# working.net
KiCad netlist of a schematic drawn in EAGLE
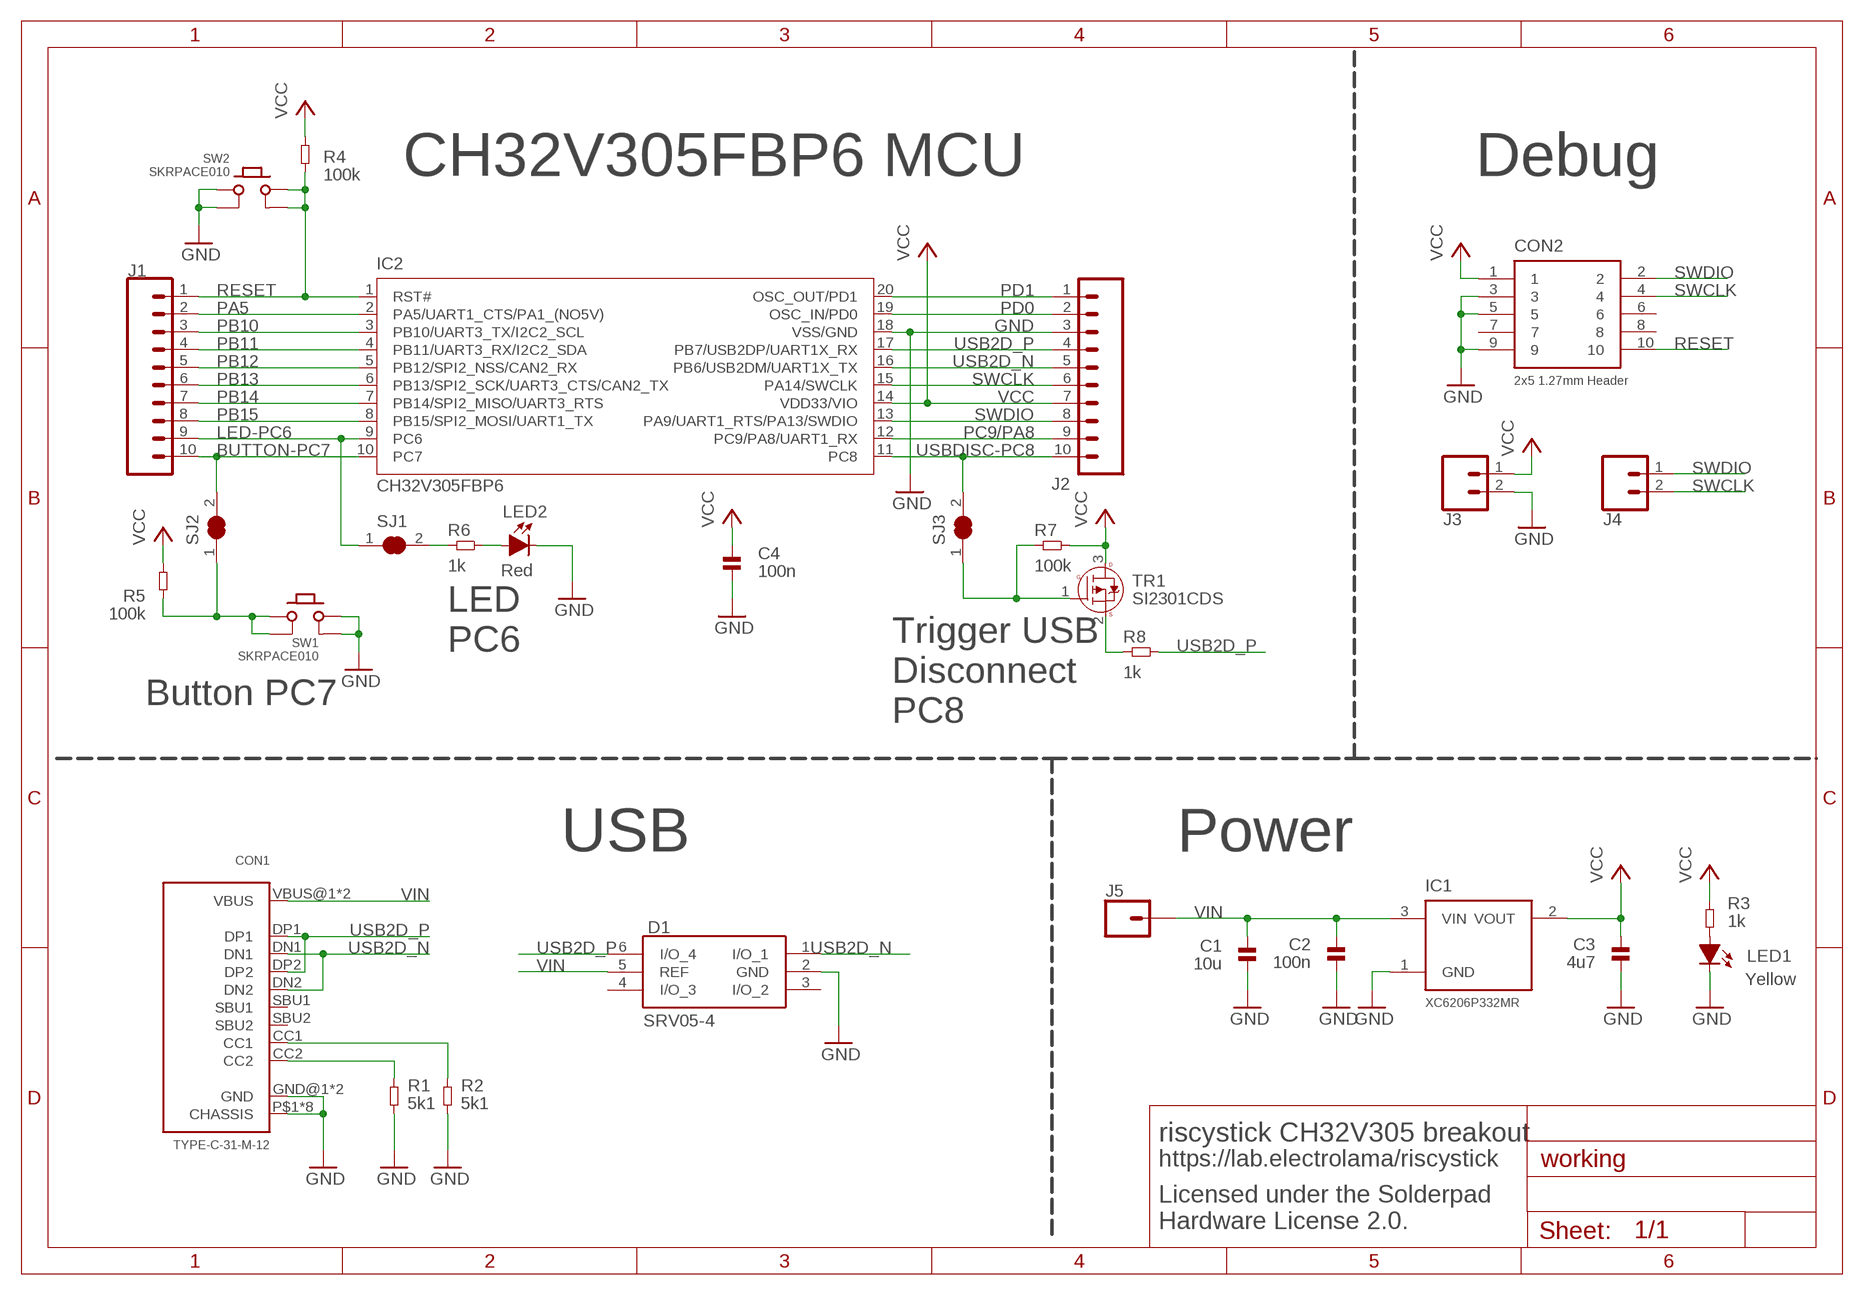
[diagram p0: schematic, sheet 1]

(export (version "E")
  (design (tool "Eeschema 10.0.6"))
  (components
    (comp (ref "C1")
      (value "10u")
      (footprint "eagle-import:_PKG_C_0603")
      (libsource (lib "eagle-import") (part "CAP-0603"))
    )
    (comp (ref "C2")
      (value "100n")
      (footprint "eagle-import:_PKG_C_0402")
      (libsource (lib "eagle-import") (part "CAP-0402"))
    )
    (comp (ref "C3")
      (value "4u7")
      (footprint "eagle-import:_PKG_C_0402")
      (libsource (lib "eagle-import") (part "CAP-0402"))
    )
    (comp (ref "C4")
      (value "100n")
      (footprint "eagle-import:_PKG_C_0402")
      (libsource (lib "eagle-import") (part "CAP-0402"))
    )
    (comp (ref "CON1")
      (value "TYPE-C-31-M-12")
      (footprint "eagle-import:USBC_C-31-M-12")
      (libsource (lib "eagle-import") (part "USBC_USB-C-12"))
    )
    (comp (ref "CON2")
      (value "2x5 1.27mm Header")
      (footprint "eagle-import:PZ127VS-12-10-H10-A38")
      (libsource (lib "eagle-import") (part "CON_1.27MM_SMD_2X5_NOSHROUD"))
    )
    (comp (ref "D1")
      (value "SRV05-4")
      (footprint "eagle-import:SOT95P280X145-6N")
      (fields (field (name "MANUFACTURER_PART_NUMBER") "SRV05-4-P-T7"))
      (libsource (lib "eagle-import") (part "DIODE-TVS-SRV05-4"))
    )
    (comp (ref "IC1")
      (value "XC6206P332MR")
      (footprint "eagle-import:SOT96P237X111-3N")
      (libsource (lib "eagle-import") (part "POWER-LDO-XC6206P???MR"))
    )
    (comp (ref "IC2")
      (value "CH32V305FBP6")
      (footprint "eagle-import:TSSOP20-WCH")
      (libsource (lib "eagle-import") (part "MCU-CH32V305F"))
    )
    (comp (ref "J1")
      (value "CONN_10LOCK")
      (footprint "eagle-import:1X10_LOCK")
      (libsource (lib "eagle-import") (part "CONN_10LOCK"))
    )
    (comp (ref "J2")
      (value "CONN_10LOCK")
      (footprint "eagle-import:1X10_LOCK")
      (libsource (lib "eagle-import") (part "CONN_10LOCK"))
    )
    (comp (ref "J3")
      (value "CONN_02LOCK")
      (footprint "eagle-import:1X02_LOCK")
      (libsource (lib "eagle-import") (part "CONN_02LOCK"))
    )
    (comp (ref "J4")
      (value "CONN_02LOCK")
      (footprint "eagle-import:1X02_LOCK")
      (libsource (lib "eagle-import") (part "CONN_02LOCK"))
    )
    (comp (ref "J5")
      (value "CONN_01")
      (footprint "eagle-import:1X01")
      (libsource (lib "eagle-import") (part "CONN_01"))
    )
    (comp (ref "LED1")
      (value "Yellow")
      (footprint "eagle-import:_PKG_LED_0805")
      (libsource (lib "eagle-import") (part "LED-0805"))
    )
    (comp (ref "LED2")
      (value "Red")
      (footprint "eagle-import:_PKG_LED_0805")
      (libsource (lib "eagle-import") (part "LED-0805"))
    )
    (comp (ref "R1")
      (value "5k1")
      (footprint "eagle-import:_PKG_R_0402")
      (libsource (lib "eagle-import") (part "RES-0402"))
    )
    (comp (ref "R2")
      (value "5k1")
      (footprint "eagle-import:_PKG_R_0402")
      (libsource (lib "eagle-import") (part "RES-0402"))
    )
    (comp (ref "R3")
      (value "1k")
      (footprint "eagle-import:_PKG_R_0402")
      (libsource (lib "eagle-import") (part "RES-0402"))
    )
    (comp (ref "R4")
      (value "100k")
      (footprint "eagle-import:_PKG_R_0402")
      (libsource (lib "eagle-import") (part "RES-0402"))
    )
    (comp (ref "R5")
      (value "100k")
      (footprint "eagle-import:_PKG_R_0402")
      (libsource (lib "eagle-import") (part "RES-0402"))
    )
    (comp (ref "R6")
      (value "1k")
      (footprint "eagle-import:_PKG_R_0402")
      (libsource (lib "eagle-import") (part "RES-0402"))
    )
    (comp (ref "R7")
      (value "100k")
      (footprint "eagle-import:_PKG_R_0402")
      (libsource (lib "eagle-import") (part "RES-0402"))
    )
    (comp (ref "R8")
      (value "1k")
      (footprint "eagle-import:_PKG_R_0402")
      (libsource (lib "eagle-import") (part "RES-0402"))
    )
    (comp (ref "SJ1")
      (value "SJ-SHORT")
      (footprint "eagle-import:SJ-SHORT")
      (libsource (lib "eagle-import") (part "SJ-SHORT"))
    )
    (comp (ref "SJ2")
      (value "SJ-SHORT")
      (footprint "eagle-import:SJ-SHORT")
      (libsource (lib "eagle-import") (part "SJ-SHORT"))
    )
    (comp (ref "SJ3")
      (value "SJ-SHORT")
      (footprint "eagle-import:SJ-SHORT")
      (libsource (lib "eagle-import") (part "SJ-SHORT"))
    )
    (comp (ref "SW1")
      (value "SKRPACE010")
      (footprint "eagle-import:PUSHBUTTON-4.2X3.2MM")
      (libsource (lib "eagle-import") (part "PUSHBUTTON-4.2X3.2MM"))
    )
    (comp (ref "SW2")
      (value "SKRPACE010")
      (footprint "eagle-import:PUSHBUTTON-4.2X3.2MM")
      (libsource (lib "eagle-import") (part "PUSHBUTTON-4.2X3.2MM"))
    )
    (comp (ref "TR1")
      (value "SI2301CDS")
      (footprint "eagle-import:SOT96P237X111-3N")
      (libsource (lib "eagle-import") (part "MOSFET-P-SI2301CDS"))
    )
  )
  (nets
    (net (code "1") (name "/BUTTON-PC7") (class "Default")
      (node (ref "IC2") (pin "10") (pinfunction "PC7_10") (pintype "bidirectional"))
      (node (ref "J1") (pin "10") (pinfunction "10_10") (pintype "passive"))
      (node (ref "SJ2") (pin "2") (pinfunction "2_2") (pintype "passive"))
    )
    (net (code "2") (name "/LED-PC6") (class "Default")
      (node (ref "IC2") (pin "9") (pinfunction "PC6_9") (pintype "bidirectional"))
      (node (ref "J1") (pin "9") (pinfunction "9_9") (pintype "passive"))
      (node (ref "SJ1") (pin "1") (pinfunction "1_1") (pintype "passive"))
    )
    (net (code "3") (name "/PA5") (class "Default")
      (node (ref "IC2") (pin "2") (pinfunction "PA5/UART1_CTS/PA1_(NO5V)_2") (pintype "bidirectional"))
      (node (ref "J1") (pin "2") (pinfunction "2_2") (pintype "passive"))
    )
    (net (code "4") (name "/PB10") (class "Default")
      (node (ref "IC2") (pin "3") (pinfunction "PB10/UART3_TX/I2C2_SCL_3") (pintype "bidirectional"))
      (node (ref "J1") (pin "3") (pinfunction "3_3") (pintype "passive"))
    )
    (net (code "5") (name "/PB11") (class "Default")
      (node (ref "IC2") (pin "4") (pinfunction "PB11/UART3_RX/I2C2_SDA_4") (pintype "bidirectional"))
      (node (ref "J1") (pin "4") (pinfunction "4_4") (pintype "passive"))
    )
    (net (code "6") (name "/PB12") (class "Default")
      (node (ref "IC2") (pin "5") (pinfunction "PB12/SPI2_NSS/CAN2_RX_5") (pintype "bidirectional"))
      (node (ref "J1") (pin "5") (pinfunction "5_5") (pintype "passive"))
    )
    (net (code "7") (name "/PB13") (class "Default")
      (node (ref "IC2") (pin "6") (pinfunction "PB13/SPI2_SCK/UART3_CTS/CAN2_TX_6") (pintype "bidirectional"))
      (node (ref "J1") (pin "6") (pinfunction "6_6") (pintype "passive"))
    )
    (net (code "8") (name "/PB14") (class "Default")
      (node (ref "IC2") (pin "7") (pinfunction "PB14/SPI2_MISO/UART3_RTS_7") (pintype "bidirectional"))
      (node (ref "J1") (pin "7") (pinfunction "7_7") (pintype "passive"))
    )
    (net (code "9") (name "/PB15") (class "Default")
      (node (ref "IC2") (pin "8") (pinfunction "PB15/SPI2_MOSI/UART1_TX_8") (pintype "bidirectional"))
      (node (ref "J1") (pin "8") (pinfunction "8_8") (pintype "passive"))
    )
    (net (code "10") (name "/PC9{slash}PA8") (class "Default")
      (node (ref "IC2") (pin "12") (pinfunction "PC9/PA8/UART1_RX_12") (pintype "bidirectional"))
      (node (ref "J2") (pin "9") (pinfunction "9_9") (pintype "passive"))
    )
    (net (code "11") (name "/PD0") (class "Default")
      (node (ref "IC2") (pin "19") (pinfunction "OSC_IN/PD0_19") (pintype "bidirectional"))
      (node (ref "J2") (pin "2") (pinfunction "2_2") (pintype "passive"))
    )
    (net (code "12") (name "/PD1") (class "Default")
      (node (ref "IC2") (pin "20") (pinfunction "OSC_OUT/PD1_20") (pintype "bidirectional"))
      (node (ref "J2") (pin "1") (pinfunction "1_1") (pintype "passive"))
    )
    (net (code "13") (name "/RESET") (class "Default")
      (node (ref "CON2") (pin "10") (pinfunction "10_10") (pintype "bidirectional"))
      (node (ref "IC2") (pin "1") (pinfunction "RST#_1") (pintype "bidirectional"))
      (node (ref "J1") (pin "1") (pinfunction "1_1") (pintype "passive"))
      (node (ref "R4") (pin "2") (pinfunction "2_2") (pintype "passive"))
      (node (ref "SW2") (pin "3") (pinfunction "2_1_3") (pintype "bidirectional"))
      (node (ref "SW2") (pin "4") (pinfunction "2_2_4") (pintype "bidirectional"))
    )
    (net (code "14") (name "/SWCLK") (class "Default")
      (node (ref "CON2") (pin "4") (pinfunction "4_4") (pintype "bidirectional"))
      (node (ref "IC2") (pin "15") (pinfunction "PA14/SWCLK_15") (pintype "bidirectional"))
      (node (ref "J2") (pin "6") (pinfunction "6_6") (pintype "passive"))
      (node (ref "J4") (pin "2") (pinfunction "2_2") (pintype "passive"))
    )
    (net (code "15") (name "/SWDIO") (class "Default")
      (node (ref "CON2") (pin "2") (pinfunction "2_2") (pintype "bidirectional"))
      (node (ref "IC2") (pin "13") (pinfunction "PA9/UART1_RTS/PA13/SWDIO_13") (pintype "bidirectional"))
      (node (ref "J2") (pin "8") (pinfunction "8_8") (pintype "passive"))
      (node (ref "J4") (pin "1") (pinfunction "1_1") (pintype "passive"))
    )
    (net (code "16") (name "/USB2D_N") (class "Default")
      (node (ref "CON1") (pin "DN1") (pinfunction "DN1_DN1") (pintype "bidirectional"))
      (node (ref "CON1") (pin "DN2") (pinfunction "DN2_DN2") (pintype "bidirectional"))
      (node (ref "D1") (pin "1") (pinfunction "I/O_1_1") (pintype "bidirectional"))
      (node (ref "IC2") (pin "16") (pinfunction "PB6/USB2DM/UART1X_TX_16") (pintype "bidirectional"))
      (node (ref "J2") (pin "5") (pinfunction "5_5") (pintype "passive"))
    )
    (net (code "17") (name "/USB2D_P") (class "Default")
      (node (ref "CON1") (pin "DP1") (pinfunction "DP1_DP1") (pintype "bidirectional"))
      (node (ref "CON1") (pin "DP2") (pinfunction "DP2_DP2") (pintype "bidirectional"))
      (node (ref "D1") (pin "6") (pinfunction "I/O_4_6") (pintype "bidirectional"))
      (node (ref "IC2") (pin "17") (pinfunction "PB7/USB2DP/UART1X_RX_17") (pintype "bidirectional"))
      (node (ref "J2") (pin "4") (pinfunction "4_4") (pintype "passive"))
      (node (ref "R8") (pin "1") (pinfunction "1_1") (pintype "passive"))
    )
    (net (code "18") (name "/USBDISC-PC8") (class "Default")
      (node (ref "IC2") (pin "11") (pinfunction "PC8_11") (pintype "bidirectional"))
      (node (ref "J2") (pin "10") (pinfunction "10_10") (pintype "passive"))
      (node (ref "SJ3") (pin "2") (pinfunction "2_2") (pintype "passive"))
    )
    (net (code "19") (name "/VIN") (class "Default")
      (node (ref "C1") (pin "1") (pinfunction "1_1") (pintype "passive"))
      (node (ref "C2") (pin "1") (pinfunction "1_1") (pintype "passive"))
      (node (ref "CON1") (pin "VBUS@1") (pinfunction "VBUS_VBUS@1") (pintype "bidirectional"))
      (node (ref "CON1") (pin "VBUS@2") (pinfunction "VBUS_VBUS@2") (pintype "bidirectional"))
      (node (ref "D1") (pin "5") (pinfunction "REF_5") (pintype "bidirectional"))
      (node (ref "IC1") (pin "3") (pinfunction "VIN_3") (pintype "bidirectional"))
      (node (ref "J5") (pin "1") (pinfunction "1_1") (pintype "passive"))
    )
    (net (code "20") (name "GND") (class "Default")
      (node (ref "C1") (pin "2") (pinfunction "2_2") (pintype "passive"))
      (node (ref "C2") (pin "2") (pinfunction "2_2") (pintype "passive"))
      (node (ref "C3") (pin "2") (pinfunction "2_2") (pintype "passive"))
      (node (ref "C4") (pin "2") (pinfunction "2_2") (pintype "passive"))
      (node (ref "CON1") (pin "GND@1") (pinfunction "GND_GND@1") (pintype "bidirectional"))
      (node (ref "CON1") (pin "GND@2") (pinfunction "GND_GND@2") (pintype "bidirectional"))
      (node (ref "CON1") (pin "P$1") (pinfunction "CHASSIS_P$1") (pintype "bidirectional"))
      (node (ref "CON1") (pin "P$2") (pinfunction "CHASSIS_P$2") (pintype "bidirectional"))
      (node (ref "CON1") (pin "P$3") (pinfunction "CHASSIS_P$3") (pintype "bidirectional"))
      (node (ref "CON1") (pin "P$4") (pinfunction "CHASSIS_P$4") (pintype "bidirectional"))
      (node (ref "CON1") (pin "P$5") (pinfunction "CHASSIS_P$5") (pintype "bidirectional"))
      (node (ref "CON1") (pin "P$6") (pinfunction "CHASSIS_P$6") (pintype "bidirectional"))
      (node (ref "CON1") (pin "P$7") (pinfunction "CHASSIS_P$7") (pintype "bidirectional"))
      (node (ref "CON1") (pin "P$8") (pinfunction "CHASSIS_P$8") (pintype "bidirectional"))
      (node (ref "CON2") (pin "3") (pinfunction "3_3") (pintype "bidirectional"))
      (node (ref "CON2") (pin "5") (pinfunction "5_5") (pintype "bidirectional"))
      (node (ref "CON2") (pin "9") (pinfunction "9_9") (pintype "bidirectional"))
      (node (ref "D1") (pin "2") (pinfunction "GND_2") (pintype "bidirectional"))
      (node (ref "IC1") (pin "1") (pinfunction "GND_1") (pintype "bidirectional"))
      (node (ref "IC2") (pin "18") (pinfunction "VSS/GND_18") (pintype "bidirectional"))
      (node (ref "J2") (pin "3") (pinfunction "3_3") (pintype "passive"))
      (node (ref "J3") (pin "2") (pinfunction "2_2") (pintype "passive"))
      (node (ref "LED1") (pin "C") (pinfunction "C_C") (pintype "passive"))
      (node (ref "LED2") (pin "C") (pinfunction "C_C") (pintype "passive"))
      (node (ref "R1") (pin "1") (pinfunction "1_1") (pintype "passive"))
      (node (ref "R2") (pin "1") (pinfunction "1_1") (pintype "passive"))
      (node (ref "SW1") (pin "3") (pinfunction "2_1_3") (pintype "bidirectional"))
      (node (ref "SW1") (pin "4") (pinfunction "2_2_4") (pintype "bidirectional"))
      (node (ref "SW2") (pin "1") (pinfunction "1_1_1") (pintype "bidirectional"))
      (node (ref "SW2") (pin "2") (pinfunction "1_2_2") (pintype "bidirectional"))
    )
    (net (code "21") (name "Net-(CON1-PadCC1)") (class "Default")
      (node (ref "CON1") (pin "CC1") (pinfunction "CC1_CC1") (pintype "bidirectional"))
      (node (ref "R2") (pin "2") (pinfunction "2_2") (pintype "passive"))
    )
    (net (code "22") (name "Net-(CON1-PadCC2)") (class "Default")
      (node (ref "CON1") (pin "CC2") (pinfunction "CC2_CC2") (pintype "bidirectional"))
      (node (ref "R1") (pin "2") (pinfunction "2_2") (pintype "passive"))
    )
    (net (code "23") (name "Net-(LED1-PadA)") (class "Default")
      (node (ref "LED1") (pin "A") (pinfunction "A_A") (pintype "passive"))
      (node (ref "R3") (pin "1") (pinfunction "1_1") (pintype "passive"))
    )
    (net (code "24") (name "Net-(LED2-PadA)") (class "Default")
      (node (ref "LED2") (pin "A") (pinfunction "A_A") (pintype "passive"))
      (node (ref "R6") (pin "1") (pinfunction "1_1") (pintype "passive"))
    )
    (net (code "25") (name "Net-(R6-Pad2)") (class "Default")
      (node (ref "R6") (pin "2") (pinfunction "2_2") (pintype "passive"))
      (node (ref "SJ1") (pin "2") (pinfunction "2_2") (pintype "passive"))
    )
    (net (code "26") (name "Net-(SW1-1_1)") (class "Default")
      (node (ref "R5") (pin "2") (pinfunction "2_2") (pintype "passive"))
      (node (ref "SJ2") (pin "1") (pinfunction "1_1") (pintype "passive"))
      (node (ref "SW1") (pin "1") (pinfunction "1_1_1") (pintype "bidirectional"))
      (node (ref "SW1") (pin "2") (pinfunction "1_2_2") (pintype "bidirectional"))
    )
    (net (code "27") (name "Net-(TR1-G)") (class "Default")
      (node (ref "R7") (pin "2") (pinfunction "2_2") (pintype "passive"))
      (node (ref "SJ3") (pin "1") (pinfunction "1_1") (pintype "passive"))
      (node (ref "TR1") (pin "1") (pinfunction "G_1") (pintype "input"))
    )
    (net (code "28") (name "Net-(TR1-S)") (class "Default")
      (node (ref "R8") (pin "2") (pinfunction "2_2") (pintype "passive"))
      (node (ref "TR1") (pin "2") (pinfunction "S_2") (pintype "input"))
    )
    (net (code "29") (name "VCC") (class "Default")
      (node (ref "C3") (pin "1") (pinfunction "1_1") (pintype "passive"))
      (node (ref "C4") (pin "1") (pinfunction "1_1") (pintype "passive"))
      (node (ref "CON2") (pin "1") (pinfunction "1_1") (pintype "bidirectional"))
      (node (ref "IC1") (pin "2") (pinfunction "VOUT_2") (pintype "bidirectional"))
      (node (ref "IC2") (pin "14") (pinfunction "VDD33/VIO_14") (pintype "bidirectional"))
      (node (ref "J2") (pin "7") (pinfunction "7_7") (pintype "passive"))
      (node (ref "J3") (pin "1") (pinfunction "1_1") (pintype "passive"))
      (node (ref "R3") (pin "2") (pinfunction "2_2") (pintype "passive"))
      (node (ref "R4") (pin "1") (pinfunction "1_1") (pintype "passive"))
      (node (ref "R5") (pin "1") (pinfunction "1_1") (pintype "passive"))
      (node (ref "R7") (pin "1") (pinfunction "1_1") (pintype "passive"))
      (node (ref "TR1") (pin "3") (pinfunction "D_3") (pintype "output"))
    )
    (net (code "30") (name "unconnected-(CON1-PadSBU1)") (class "Default")
      (node (ref "CON1") (pin "SBU1") (pinfunction "SBU1_SBU1") (pintype "bidirectional"))
    )
    (net (code "31") (name "unconnected-(CON1-PadSBU2)") (class "Default")
      (node (ref "CON1") (pin "SBU2") (pinfunction "SBU2_SBU2") (pintype "bidirectional"))
    )
    (net (code "32") (name "unconnected-(CON2-Pad6)") (class "Default")
      (node (ref "CON2") (pin "6") (pinfunction "6_6") (pintype "bidirectional"))
    )
    (net (code "33") (name "unconnected-(CON2-Pad7)") (class "Default")
      (node (ref "CON2") (pin "7") (pinfunction "7_7") (pintype "bidirectional"))
    )
    (net (code "34") (name "unconnected-(CON2-Pad8)") (class "Default")
      (node (ref "CON2") (pin "8") (pinfunction "8_8") (pintype "bidirectional"))
    )
    (net (code "35") (name "unconnected-(D1-I{slash}O_2-Pad3)") (class "Default")
      (node (ref "D1") (pin "3") (pinfunction "I/O_2_3") (pintype "bidirectional"))
    )
    (net (code "36") (name "unconnected-(D1-I{slash}O_3-Pad4)") (class "Default")
      (node (ref "D1") (pin "4") (pinfunction "I/O_3_4") (pintype "bidirectional"))
    )
  )
)
